# ecg.net
KiCad netlist of a schematic drawn in EAGLE
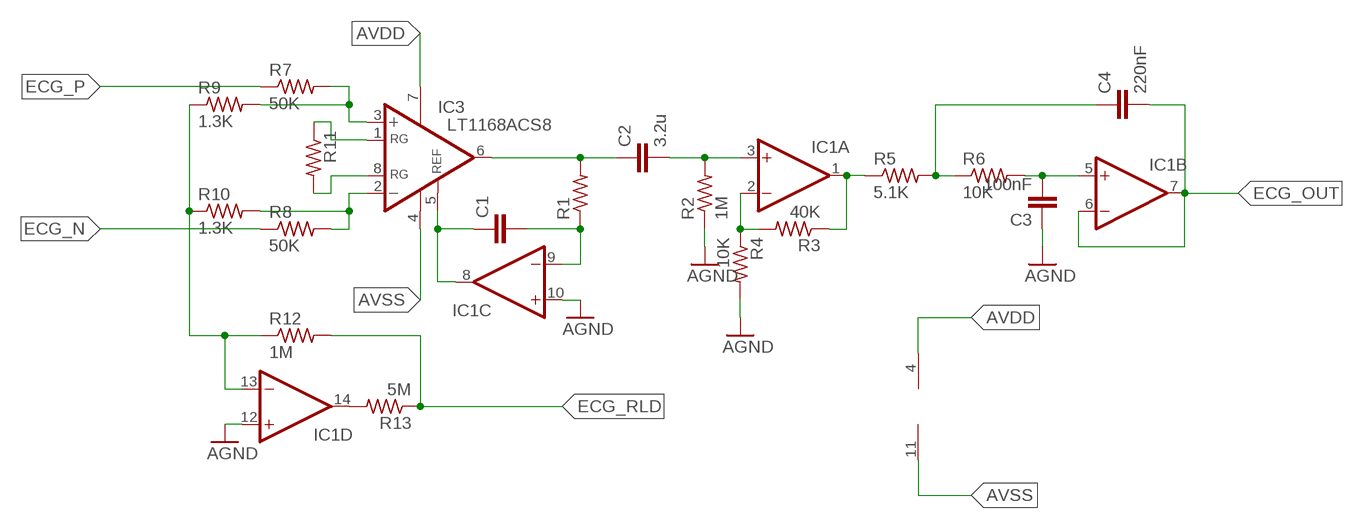
[diagram p0: schematic, sheet 1]

(export (version "E")
  (design (tool "Eeschema 10.0.6"))
  (components
    (comp (ref "C1")
      (value "CAPEZ")
      (footprint "eagle-import:CAP-PTH-SMALLEZ")
      (libsource (lib "eagle-import") (part "CAPEZ"))
    )
    (comp (ref "C2")
      (value "3.2u")
      (footprint "eagle-import:CAP-PTH-SMALLEZ")
      (libsource (lib "eagle-import") (part "CAPEZ"))
    )
    (comp (ref "C3")
      (value "100nF")
      (footprint "eagle-import:CAP-PTH-SMALLEZ")
      (libsource (lib "eagle-import") (part "CAPEZ"))
    )
    (comp (ref "C4")
      (value "220nF")
      (footprint "eagle-import:CAP-PTH-SMALLEZ")
      (libsource (lib "eagle-import") (part "CAPEZ"))
    )
    (comp (ref "IC1")
      (value "4AMP_P4+11N")
      (footprint "eagle-import:DIL14")
      (libsource (lib "eagle-import") (part "4AMP_P4+11N"))
    )
    (comp (ref "IC3")
      (value "LT1168ACS8")
      (footprint "eagle-import:SOIC8")
      (libsource (lib "eagle-import") (part "LT1168S8AC"))
    )
    (comp (ref "R1")
      (value "R-US_0204/5")
      (footprint "eagle-import:0204_5")
      (libsource (lib "eagle-import") (part "R-US_0204/5"))
    )
    (comp (ref "R2")
      (value "1M")
      (footprint "eagle-import:0204_5")
      (libsource (lib "eagle-import") (part "R-US_0204/5"))
    )
    (comp (ref "R3")
      (value "40K")
      (footprint "eagle-import:0204_5")
      (libsource (lib "eagle-import") (part "R-US_0204/5"))
    )
    (comp (ref "R4")
      (value "10K")
      (footprint "eagle-import:0204_5")
      (libsource (lib "eagle-import") (part "R-US_0204/5"))
    )
    (comp (ref "R5")
      (value "5.1K")
      (footprint "eagle-import:0204_5")
      (libsource (lib "eagle-import") (part "R-US_0204/5"))
    )
    (comp (ref "R6")
      (value "10K")
      (footprint "eagle-import:0204_5")
      (libsource (lib "eagle-import") (part "R-US_0204/5"))
    )
    (comp (ref "R7")
      (value "50K")
      (footprint "eagle-import:0204_5")
      (libsource (lib "eagle-import") (part "R-US_0204/5"))
    )
    (comp (ref "R8")
      (value "50K")
      (footprint "eagle-import:0204_5")
      (libsource (lib "eagle-import") (part "R-US_0204/5"))
    )
    (comp (ref "R9")
      (value "1.3K")
      (footprint "eagle-import:0204_5")
      (libsource (lib "eagle-import") (part "R-US_0204/5"))
    )
    (comp (ref "R10")
      (value "1.3K")
      (footprint "eagle-import:0204_5")
      (libsource (lib "eagle-import") (part "R-US_0204/5"))
    )
    (comp (ref "R11")
      (value "R-US_0204/5")
      (footprint "eagle-import:0204_5")
      (libsource (lib "eagle-import") (part "R-US_0204/5"))
    )
    (comp (ref "R12")
      (value "1M")
      (footprint "eagle-import:0204_5")
      (libsource (lib "eagle-import") (part "R-US_0204/5"))
    )
    (comp (ref "R13")
      (value "5M")
      (footprint "eagle-import:0204_5")
      (libsource (lib "eagle-import") (part "R-US_0204/5"))
    )
  )
  (nets
    (net (code "1") (name "AGND") (class "Default")
      (node (ref "C3") (pin "1") (pinfunction "1_1") (pintype "passive"))
      (node (ref "IC1") (pin "10") (pinfunction "+IN_10") (pintype "input"))
      (node (ref "IC1") (pin "12") (pinfunction "+IN_12") (pintype "input"))
      (node (ref "R2") (pin "1") (pinfunction "1_1") (pintype "passive"))
      (node (ref "R4") (pin "2") (pinfunction "2_2") (pintype "passive"))
    )
    (net (code "2") (name "AVDD") (class "Default")
      (node (ref "IC1") (pin "4") (pinfunction "V+_4") (pintype "power_in"))
      (node (ref "IC3") (pin "7") (pinfunction "V+_7") (pintype "power_in"))
    )
    (net (code "3") (name "AVSS") (class "Default")
      (node (ref "IC1") (pin "11") (pinfunction "V-_11") (pintype "power_in"))
      (node (ref "IC3") (pin "4") (pinfunction "V-_4") (pintype "power_in"))
    )
    (net (code "4") (name "ECG_N") (class "Default")
      (node (ref "R8") (pin "1") (pinfunction "1_1") (pintype "passive"))
    )
    (net (code "5") (name "ECG_OUT") (class "Default")
      (node (ref "C4") (pin "2") (pinfunction "2_2") (pintype "passive"))
      (node (ref "IC1") (pin "6") (pinfunction "-IN_6") (pintype "input"))
      (node (ref "IC1") (pin "7") (pinfunction "OUT_7") (pintype "output"))
    )
    (net (code "6") (name "ECG_P") (class "Default")
      (node (ref "R7") (pin "1") (pinfunction "1_1") (pintype "passive"))
    )
    (net (code "7") (name "ECG_RLD") (class "Default")
      (node (ref "R12") (pin "2") (pinfunction "2_2") (pintype "passive"))
      (node (ref "R13") (pin "1") (pinfunction "1_1") (pintype "passive"))
    )
    (net (code "8") (name "Net-(C4-Pad1)") (class "Default")
      (node (ref "C4") (pin "1") (pinfunction "1_1") (pintype "passive"))
      (node (ref "R5") (pin "2") (pinfunction "2_2") (pintype "passive"))
      (node (ref "R6") (pin "1") (pinfunction "1_1") (pintype "passive"))
    )
    (net (code "9") (name "Net-(IC1A-+IN)") (class "Default")
      (node (ref "C2") (pin "2") (pinfunction "2_2") (pintype "passive"))
      (node (ref "IC1") (pin "3") (pinfunction "+IN_3") (pintype "input"))
      (node (ref "R2") (pin "2") (pinfunction "2_2") (pintype "passive"))
    )
    (net (code "10") (name "Net-(IC1A--IN)") (class "Default")
      (node (ref "IC1") (pin "2") (pinfunction "-IN_2") (pintype "input"))
      (node (ref "R3") (pin "2") (pinfunction "2_2") (pintype "passive"))
      (node (ref "R4") (pin "1") (pinfunction "1_1") (pintype "passive"))
    )
    (net (code "11") (name "Net-(IC1A-OUT)") (class "Default")
      (node (ref "IC1") (pin "1") (pinfunction "OUT_1") (pintype "output"))
      (node (ref "R3") (pin "1") (pinfunction "1_1") (pintype "passive"))
      (node (ref "R5") (pin "1") (pinfunction "1_1") (pintype "passive"))
    )
    (net (code "12") (name "Net-(IC1B-+IN)") (class "Default")
      (node (ref "C3") (pin "2") (pinfunction "2_2") (pintype "passive"))
      (node (ref "IC1") (pin "5") (pinfunction "+IN_5") (pintype "input"))
      (node (ref "R6") (pin "2") (pinfunction "2_2") (pintype "passive"))
    )
    (net (code "13") (name "Net-(IC1C--IN)") (class "Default")
      (node (ref "C1") (pin "2") (pinfunction "2_2") (pintype "passive"))
      (node (ref "IC1") (pin "9") (pinfunction "-IN_9") (pintype "input"))
      (node (ref "R1") (pin "1") (pinfunction "1_1") (pintype "passive"))
    )
    (net (code "14") (name "Net-(IC1C-OUT)") (class "Default")
      (node (ref "C1") (pin "1") (pinfunction "1_1") (pintype "passive"))
      (node (ref "IC1") (pin "8") (pinfunction "OUT_8") (pintype "output"))
      (node (ref "IC3") (pin "5") (pinfunction "REF_5") (pintype "input"))
    )
    (net (code "15") (name "Net-(IC1D--IN)") (class "Default")
      (node (ref "IC1") (pin "13") (pinfunction "-IN_13") (pintype "input"))
      (node (ref "R10") (pin "1") (pinfunction "1_1") (pintype "passive"))
      (node (ref "R12") (pin "1") (pinfunction "1_1") (pintype "passive"))
      (node (ref "R9") (pin "1") (pinfunction "1_1") (pintype "passive"))
    )
    (net (code "16") (name "Net-(IC1D-OUT)") (class "Default")
      (node (ref "IC1") (pin "14") (pinfunction "OUT_14") (pintype "output"))
      (node (ref "R13") (pin "2") (pinfunction "2_2") (pintype "passive"))
    )
    (net (code "17") (name "Net-(IC3-+IN)") (class "Default")
      (node (ref "IC3") (pin "3") (pinfunction "+IN_3") (pintype "input"))
      (node (ref "R7") (pin "2") (pinfunction "2_2") (pintype "passive"))
      (node (ref "R9") (pin "2") (pinfunction "2_2") (pintype "passive"))
    )
    (net (code "18") (name "Net-(IC3--IN)") (class "Default")
      (node (ref "IC3") (pin "2") (pinfunction "-IN_2") (pintype "input"))
      (node (ref "R10") (pin "2") (pinfunction "2_2") (pintype "passive"))
      (node (ref "R8") (pin "2") (pinfunction "2_2") (pintype "passive"))
    )
    (net (code "19") (name "Net-(IC3-OUT)") (class "Default")
      (node (ref "C2") (pin "1") (pinfunction "1_1") (pintype "passive"))
      (node (ref "IC3") (pin "6") (pinfunction "OUT_6") (pintype "output"))
      (node (ref "R1") (pin "2") (pinfunction "2_2") (pintype "passive"))
    )
    (net (code "20") (name "Net-(IC3-RG-Pad1)") (class "Default")
      (node (ref "IC3") (pin "1") (pinfunction "RG_1") (pintype "input"))
      (node (ref "R11") (pin "1") (pinfunction "1_1") (pintype "passive"))
    )
    (net (code "21") (name "Net-(IC3-RG-Pad8)") (class "Default")
      (node (ref "IC3") (pin "8") (pinfunction "RG_8") (pintype "input"))
      (node (ref "R11") (pin "2") (pinfunction "2_2") (pintype "passive"))
    )
  )
)
